# RS232_IrDA.net
KiCad netlist of a schematic drawn in Altium Designer
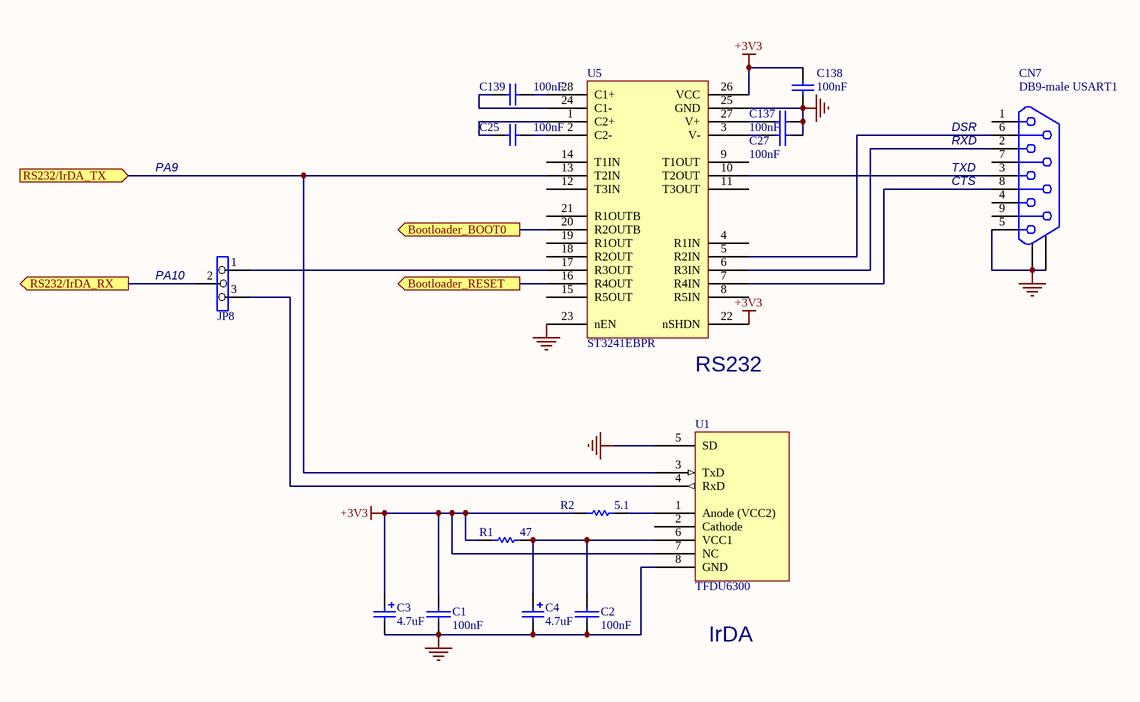
[diagram p0: RS232&IrDA.SchDoc]

(export (version "E")
  (design (tool "Eeschema 10.0.6"))
  (components
    (comp (ref "C1")
      (value "100nF")
      (footprint "0603C")
      (description "Capacitor")
      (libsource (lib "*") (part "CAP"))
    )
    (comp (ref "C2")
      (value "100nF")
      (footprint "0603C")
      (description "Capacitor")
      (libsource (lib "*") (part "CAP"))
    )
    (comp (ref "C3")
      (value "4.7uF")
      (footprint "TAN-A")
      (description "Polarized Capacitor (Radial)")
      (fields (field (name "PUBLISHER") "Altium Limited"))
      (libsource (lib "Miscellaneous Devices") (part "Cap Pol1"))
    )
    (comp (ref "C4")
      (value "4.7uF")
      (footprint "TAN-A")
      (description "Polarized Capacitor (Radial)")
      (fields (field (name "PUBLISHER") "Altium Limited"))
      (libsource (lib "Miscellaneous Devices") (part "Cap Pol1"))
    )
    (comp (ref "C25")
      (value "100nF")
      (footprint "0603C")
      (description "Capacitor")
      (fields (field (name "PUBLISHER") "Altium Limited"))
      (libsource (lib "Miscellaneous Devices") (part "Cap"))
    )
    (comp (ref "C27")
      (value "100nF")
      (footprint "0603C")
      (description "Capacitor")
      (fields (field (name "PUBLISHER") "Altium Limited"))
      (libsource (lib "Miscellaneous Devices") (part "Cap"))
    )
    (comp (ref "C137")
      (value "100nF")
      (footprint "0603C")
      (description "Capacitor")
      (fields (field (name "PUBLISHER") "Altium Limited"))
      (libsource (lib "Miscellaneous Devices") (part "Cap"))
    )
    (comp (ref "C138")
      (value "100nF")
      (footprint "0603C")
      (description "Capacitor")
      (fields (field (name "PUBLISHER") "Altium Limited"))
      (libsource (lib "Miscellaneous Devices") (part "Cap"))
    )
    (comp (ref "C139")
      (value "100nF")
      (footprint "0603C")
      (description "Capacitor")
      (fields (field (name "PUBLISHER") "Altium Limited"))
      (libsource (lib "Miscellaneous Devices") (part "Cap"))
    )
    (comp (ref "CN7")
      (value "DB9-male USART1")
      (footprint "DB9/M")
      (libsource (lib "mb1045") (part "DB9-USART"))
    )
    (comp (ref "JP8") (value "~") (footprint "SIP3") (libsource (lib "STR910_SCHLIB") (part "Jumper3")))
    (comp (ref "R1")
      (value "47")
      (footprint "0603R")
      (description "Resistor")
      (fields (field (name "PUBLISHER") "Altium Limited"))
      (libsource (lib "Miscellaneous Devices") (part "Res1"))
    )
    (comp (ref "R2")
      (value "5.1")
      (footprint "0603R")
      (description "Resistor")
      (fields (field (name "PUBLISHER") "Altium Limited"))
      (libsource (lib "Miscellaneous Devices") (part "Res1"))
    )
    (comp (ref "U1")
      (value "TFDU6300")
      (footprint "IR_VISHAY3")
      (description "TFDU4300")
      (libsource (lib "*") (part "TFDU4300"))
    )
    (comp (ref "U5")
      (value "ST3241EBPR")
      (footprint "SSOP28_0R65_10R2X7R8")
      (libsource (lib "*") (part "ST3241"))
    )
  )
  (nets
    (net (code "1") (name "+3V3") (class "Default")
      (node (ref "C1") (pin "1") (pinfunction "1_1") (pintype "passive"))
      (node (ref "C138") (pin "1") (pinfunction "1_1") (pintype "passive"))
      (node (ref "C3") (pin "1") (pinfunction "1_1") (pintype "passive"))
      (node (ref "R1") (pin "1") (pinfunction "1_1") (pintype "passive"))
      (node (ref "R2") (pin "1") (pinfunction "1_1") (pintype "passive"))
      (node (ref "U1") (pin "7") (pinfunction "NC_7") (pintype "passive"))
      (node (ref "U5") (pin "22") (pinfunction "nSHDN_22") (pintype "passive"))
      (node (ref "U5") (pin "26") (pinfunction "VCC_26") (pintype "passive"))
    )
    (net (code "2") (name "/Bootloader_BOOT0") (class "Default")
      (node (ref "U5") (pin "20") (pinfunction "R2OUTB_20") (pintype "passive"))
    )
    (net (code "3") (name "/Bootloader_RESET") (class "Default")
      (node (ref "U5") (pin "16") (pinfunction "R4OUT_16") (pintype "passive"))
    )
    (net (code "4") (name "/RS232{slash}IrDA_RX") (class "Default")
      (node (ref "JP8") (pin "2") (pintype "passive"))
    )
    (net (code "5") (name "/RS232{slash}IrDA_TX") (class "Default")
      (node (ref "U1") (pin "3") (pinfunction "TxD_3") (pintype "input"))
      (node (ref "U5") (pin "13") (pinfunction "T2IN_13") (pintype "passive"))
    )
    (net (code "6") (name "GND") (class "Default")
      (node (ref "C1") (pin "2") (pinfunction "2_2") (pintype "passive"))
      (node (ref "C137") (pin "1") (pinfunction "1_1") (pintype "passive"))
      (node (ref "C138") (pin "2") (pinfunction "2_2") (pintype "passive"))
      (node (ref "C2") (pin "2") (pinfunction "2_2") (pintype "passive"))
      (node (ref "C27") (pin "1") (pinfunction "1_1") (pintype "passive"))
      (node (ref "C3") (pin "2") (pinfunction "2_2") (pintype "passive"))
      (node (ref "C4") (pin "2") (pinfunction "2_2") (pintype "passive"))
      (node (ref "CN7") (pin "10") (pinfunction "10_10") (pintype "passive"))
      (node (ref "CN7") (pin "11") (pinfunction "11_11") (pintype "passive"))
      (node (ref "CN7") (pin "5") (pinfunction "5_5") (pintype "passive"))
      (node (ref "U1") (pin "5") (pinfunction "SD_5") (pintype "passive"))
      (node (ref "U1") (pin "8") (pinfunction "GND_8") (pintype "passive"))
      (node (ref "U5") (pin "23") (pinfunction "nEN_23") (pintype "passive"))
      (node (ref "U5") (pin "25") (pinfunction "GND_25") (pintype "passive"))
    )
    (net (code "7") (name "Net-(U1-Anode_(VCC2))") (class "Default")
      (node (ref "R2") (pin "2") (pinfunction "2_2") (pintype "passive"))
      (node (ref "U1") (pin "1") (pinfunction "Anode_(VCC2)_1") (pintype "passive"))
    )
    (net (code "8") (name "Net-(U1-RxD)") (class "Default")
      (node (ref "JP8") (pin "3") (pintype "passive"))
      (node (ref "U1") (pin "4") (pinfunction "RxD_4") (pintype "output"))
    )
    (net (code "9") (name "Net-(U1-VCC1)") (class "Default")
      (node (ref "C2") (pin "1") (pinfunction "1_1") (pintype "passive"))
      (node (ref "C4") (pin "1") (pinfunction "1_1") (pintype "passive"))
      (node (ref "R1") (pin "2") (pinfunction "2_2") (pintype "passive"))
      (node (ref "U1") (pin "6") (pinfunction "VCC1_6") (pintype "passive"))
    )
    (net (code "10") (name "Net-(U5-C1+)") (class "Default")
      (node (ref "C139") (pin "2") (pinfunction "2_2") (pintype "passive"))
      (node (ref "U5") (pin "28") (pinfunction "C1+_28") (pintype "passive"))
    )
    (net (code "11") (name "Net-(U5-C1-)") (class "Default")
      (node (ref "C139") (pin "1") (pinfunction "1_1") (pintype "passive"))
      (node (ref "U5") (pin "24") (pinfunction "C1-_24") (pintype "passive"))
    )
    (net (code "12") (name "Net-(U5-C2+)") (class "Default")
      (node (ref "C25") (pin "1") (pinfunction "1_1") (pintype "passive"))
      (node (ref "U5") (pin "1") (pinfunction "C2+_1") (pintype "passive"))
    )
    (net (code "13") (name "Net-(U5-C2-)") (class "Default")
      (node (ref "C25") (pin "2") (pinfunction "2_2") (pintype "passive"))
      (node (ref "U5") (pin "2") (pinfunction "C2-_2") (pintype "passive"))
    )
    (net (code "14") (name "Net-(U5-R2IN)") (class "Default")
      (node (ref "CN7") (pin "6") (pinfunction "6_6") (pintype "passive"))
      (node (ref "U5") (pin "5") (pinfunction "R2IN_5") (pintype "passive"))
    )
    (net (code "15") (name "Net-(U5-R3IN)") (class "Default")
      (node (ref "CN7") (pin "2") (pinfunction "2_2") (pintype "passive"))
      (node (ref "U5") (pin "6") (pinfunction "R3IN_6") (pintype "passive"))
    )
    (net (code "16") (name "Net-(U5-R3OUT)") (class "Default")
      (node (ref "JP8") (pin "1") (pintype "passive"))
      (node (ref "U5") (pin "17") (pinfunction "R3OUT_17") (pintype "passive"))
    )
    (net (code "17") (name "Net-(U5-R4IN)") (class "Default")
      (node (ref "CN7") (pin "8") (pinfunction "8_8") (pintype "passive"))
      (node (ref "U5") (pin "7") (pinfunction "R4IN_7") (pintype "passive"))
    )
    (net (code "18") (name "Net-(U5-T2OUT)") (class "Default")
      (node (ref "CN7") (pin "3") (pinfunction "3_3") (pintype "passive"))
      (node (ref "U5") (pin "10") (pinfunction "T2OUT_10") (pintype "passive"))
    )
    (net (code "19") (name "Net-(U5-V+)") (class "Default")
      (node (ref "C137") (pin "2") (pinfunction "2_2") (pintype "passive"))
      (node (ref "U5") (pin "27") (pinfunction "V+_27") (pintype "passive"))
    )
    (net (code "20") (name "Net-(U5-V-)") (class "Default")
      (node (ref "C27") (pin "2") (pinfunction "2_2") (pintype "passive"))
      (node (ref "U5") (pin "3") (pinfunction "V-_3") (pintype "passive"))
    )
    (net (code "21") (name "unconnected-(CN7-Pad1)") (class "Default")
      (node (ref "CN7") (pin "1") (pinfunction "1_1") (pintype "passive"))
    )
    (net (code "22") (name "unconnected-(CN7-Pad4)") (class "Default")
      (node (ref "CN7") (pin "4") (pinfunction "4_4") (pintype "passive"))
    )
    (net (code "23") (name "unconnected-(CN7-Pad7)") (class "Default")
      (node (ref "CN7") (pin "7") (pinfunction "7_7") (pintype "passive"))
    )
    (net (code "24") (name "unconnected-(CN7-Pad9)") (class "Default")
      (node (ref "CN7") (pin "9") (pinfunction "9_9") (pintype "passive"))
    )
    (net (code "25") (name "unconnected-(U1-Cathode-Pad2)") (class "Default")
      (node (ref "U1") (pin "2") (pinfunction "Cathode_2") (pintype "passive"))
    )
    (net (code "26") (name "unconnected-(U5-R1IN-Pad4)") (class "Default")
      (node (ref "U5") (pin "4") (pinfunction "R1IN_4") (pintype "passive"))
    )
    (net (code "27") (name "unconnected-(U5-R1OUT-Pad19)") (class "Default")
      (node (ref "U5") (pin "19") (pinfunction "R1OUT_19") (pintype "passive"))
    )
    (net (code "28") (name "unconnected-(U5-R1OUTB-Pad21)") (class "Default")
      (node (ref "U5") (pin "21") (pinfunction "R1OUTB_21") (pintype "passive"))
    )
    (net (code "29") (name "unconnected-(U5-R2OUT-Pad18)") (class "Default")
      (node (ref "U5") (pin "18") (pinfunction "R2OUT_18") (pintype "passive"))
    )
    (net (code "30") (name "unconnected-(U5-R5IN-Pad8)") (class "Default")
      (node (ref "U5") (pin "8") (pinfunction "R5IN_8") (pintype "passive"))
    )
    (net (code "31") (name "unconnected-(U5-R5OUT-Pad15)") (class "Default")
      (node (ref "U5") (pin "15") (pinfunction "R5OUT_15") (pintype "passive"))
    )
    (net (code "32") (name "unconnected-(U5-T1IN-Pad14)") (class "Default")
      (node (ref "U5") (pin "14") (pinfunction "T1IN_14") (pintype "passive"))
    )
    (net (code "33") (name "unconnected-(U5-T1OUT-Pad9)") (class "Default")
      (node (ref "U5") (pin "9") (pinfunction "T1OUT_9") (pintype "passive"))
    )
    (net (code "34") (name "unconnected-(U5-T3IN-Pad12)") (class "Default")
      (node (ref "U5") (pin "12") (pinfunction "T3IN_12") (pintype "passive"))
    )
    (net (code "35") (name "unconnected-(U5-T3OUT-Pad11)") (class "Default")
      (node (ref "U5") (pin "11") (pinfunction "T3OUT_11") (pintype "passive"))
    )
  )
)
